# RHD2132_lvds_headstage_neuroengenharia_v.net
KiCad netlist of a schematic drawn in EAGLE
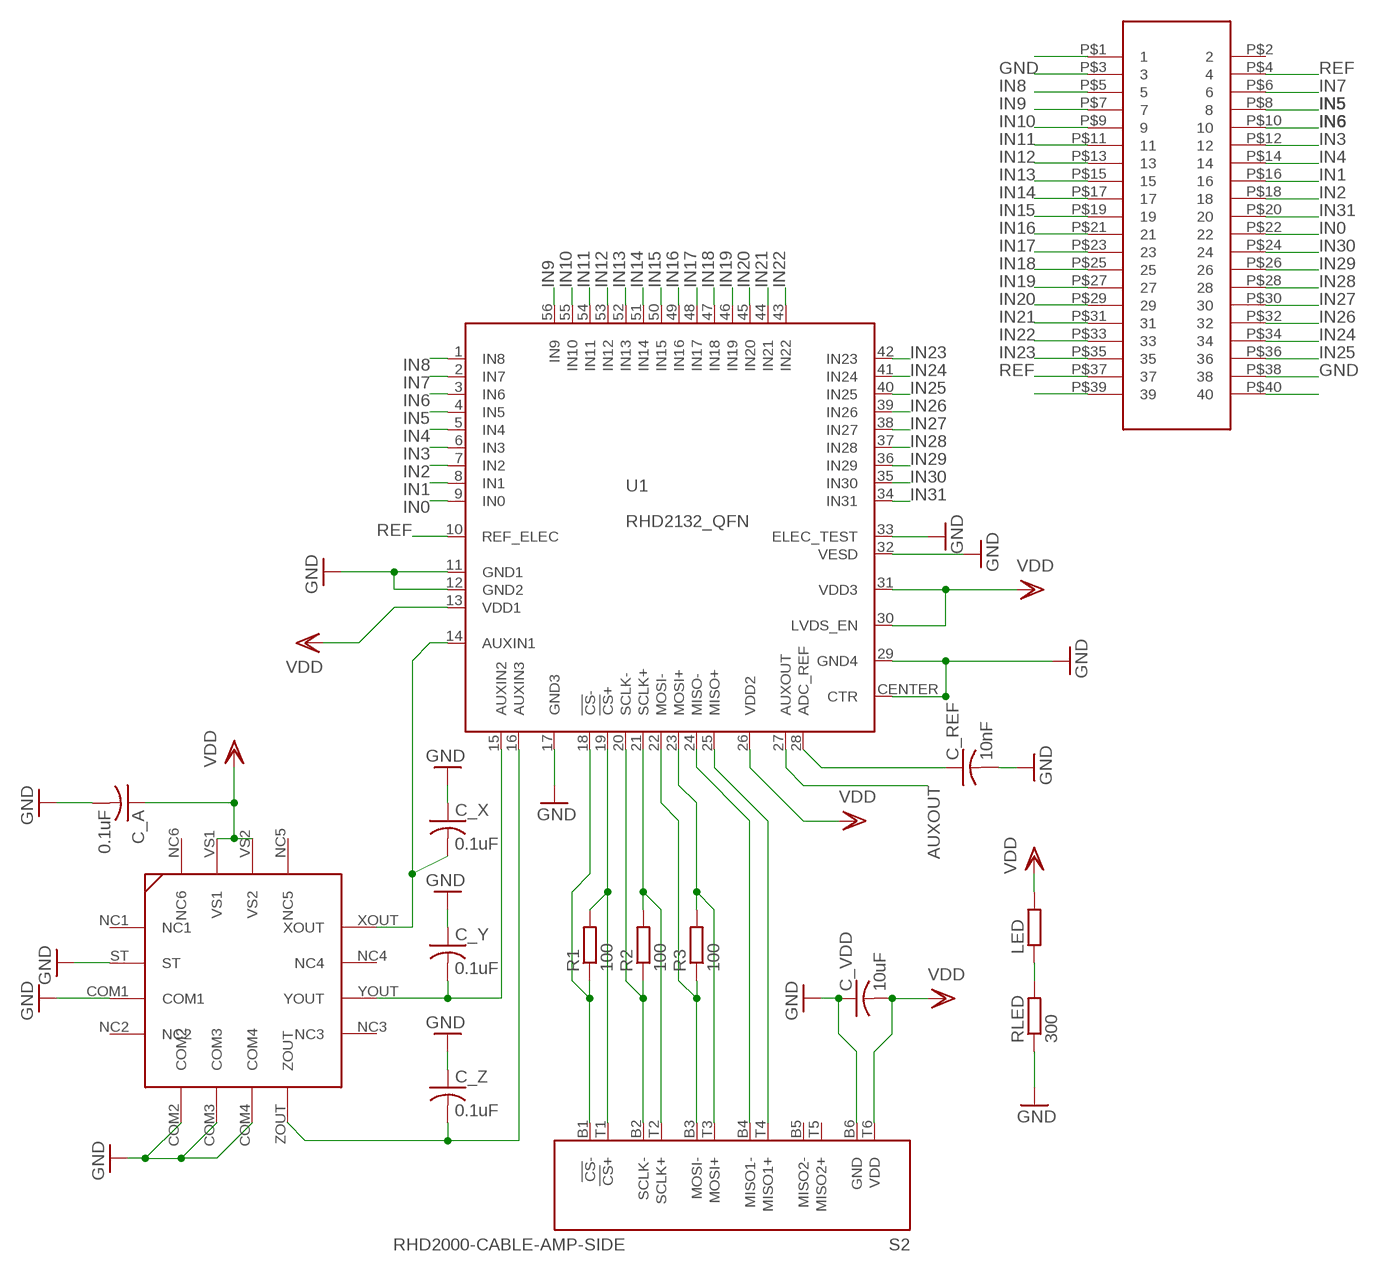
[diagram p0: schematic, sheet 1]

(export (version "E")
  (design (tool "Eeschema 10.0.6"))
  (components
    (comp (ref "C_A")
      (value "0.1uF")
      (footprint "eagle-import:C0402K")
      (libsource (lib "eagle-import") (part "C-USC0402K"))
    )
    (comp (ref "C_REF")
      (value "10nF")
      (footprint "eagle-import:C0402K")
      (libsource (lib "eagle-import") (part "C-USC0402K"))
    )
    (comp (ref "C_VDD")
      (value "10uF")
      (footprint "eagle-import:C0402K")
      (libsource (lib "eagle-import") (part "C-USC0402K"))
    )
    (comp (ref "C_X")
      (value "0.1uF")
      (footprint "eagle-import:C0402K")
      (libsource (lib "eagle-import") (part "C-USC0402K"))
    )
    (comp (ref "C_Y")
      (value "0.1uF")
      (footprint "eagle-import:C0402K")
      (libsource (lib "eagle-import") (part "C-USC0402K"))
    )
    (comp (ref "C_Z")
      (value "0.1uF")
      (footprint "eagle-import:C0402K")
      (libsource (lib "eagle-import") (part "C-USC0402K"))
    )
    (comp (ref "LED")
      (value "R-EU_R0402")
      (footprint "eagle-import:R0402")
      (libsource (lib "eagle-import") (part "R-EU_R0402"))
    )
    (comp (ref "R1")
      (value "100")
      (footprint "eagle-import:R0402")
      (libsource (lib "eagle-import") (part "R-EU_R0402"))
    )
    (comp (ref "R2")
      (value "100")
      (footprint "eagle-import:R0402")
      (libsource (lib "eagle-import") (part "R-EU_R0402"))
    )
    (comp (ref "R3")
      (value "100")
      (footprint "eagle-import:R0402")
      (libsource (lib "eagle-import") (part "R-EU_R0402"))
    )
    (comp (ref "RLED")
      (value "300")
      (footprint "eagle-import:R0402")
      (libsource (lib "eagle-import") (part "R-EU_R0402"))
    )
    (comp (ref "S2")
      (value "RHD2000-CABLE-AMP-SIDE")
      (footprint "eagle-import:OMNETICS_PZN-12-AA")
      (libsource (lib "eagle-import") (part "RHD2000-CABLE-AMP-SIDE"))
    )
    (comp (ref "U$1")
      (value "ADXL335")
      (footprint "eagle-import:ADXL335")
      (libsource (lib "eagle-import") (part "ADXL335"))
    )
    (comp (ref "U$2")
      (value "MOLEX_552010478")
      (footprint "eagle-import:MOLEX")
      (libsource (lib "eagle-import") (part "MOLEX_552010478"))
    )
    (comp (ref "U1")
      (value "RHD2132_QFN")
      (footprint "eagle-import:QFN56_8_X_8_LARGE")
      (libsource (lib "eagle-import") (part "RHD2132_QFN"))
    )
  )
  (nets
    (net (code "1") (name "/AUXOUT") (class "Default")
      (node (ref "U1") (pin "27") (pinfunction "AUXOUT_27") (pintype "tri_state"))
    )
    (net (code "2") (name "/IN0") (class "Default")
      (node (ref "U$2") (pin "P$22") (pinfunction "22_P$22") (pintype "bidirectional"))
      (node (ref "U1") (pin "9") (pinfunction "IN0_9") (pintype "input"))
    )
    (net (code "3") (name "/IN1") (class "Default")
      (node (ref "U$2") (pin "P$16") (pinfunction "16_P$16") (pintype "bidirectional"))
      (node (ref "U1") (pin "8") (pinfunction "IN1_8") (pintype "input"))
    )
    (net (code "4") (name "/IN2") (class "Default")
      (node (ref "U$2") (pin "P$18") (pinfunction "18_P$18") (pintype "bidirectional"))
      (node (ref "U1") (pin "7") (pinfunction "IN2_7") (pintype "input"))
    )
    (net (code "5") (name "/IN3") (class "Default")
      (node (ref "U$2") (pin "P$12") (pinfunction "12_P$12") (pintype "bidirectional"))
      (node (ref "U1") (pin "6") (pinfunction "IN3_6") (pintype "input"))
    )
    (net (code "6") (name "/IN4") (class "Default")
      (node (ref "U$2") (pin "P$14") (pinfunction "14_P$14") (pintype "bidirectional"))
      (node (ref "U1") (pin "5") (pinfunction "IN4_5") (pintype "input"))
    )
    (net (code "7") (name "/IN5") (class "Default")
      (node (ref "U$2") (pin "P$8") (pinfunction "8_P$8") (pintype "bidirectional"))
      (node (ref "U1") (pin "4") (pinfunction "IN5_4") (pintype "input"))
    )
    (net (code "8") (name "/IN6") (class "Default")
      (node (ref "U$2") (pin "P$10") (pinfunction "10_P$10") (pintype "bidirectional"))
      (node (ref "U1") (pin "3") (pinfunction "IN6_3") (pintype "input"))
    )
    (net (code "9") (name "/IN7") (class "Default")
      (node (ref "U$2") (pin "P$6") (pinfunction "6_P$6") (pintype "bidirectional"))
      (node (ref "U1") (pin "2") (pinfunction "IN7_2") (pintype "input"))
    )
    (net (code "10") (name "/IN8") (class "Default")
      (node (ref "U$2") (pin "P$5") (pinfunction "5_P$5") (pintype "bidirectional"))
      (node (ref "U1") (pin "1") (pinfunction "IN8_1") (pintype "input"))
    )
    (net (code "11") (name "/IN9") (class "Default")
      (node (ref "U$2") (pin "P$7") (pinfunction "7_P$7") (pintype "bidirectional"))
      (node (ref "U1") (pin "56") (pinfunction "IN9_56") (pintype "input"))
    )
    (net (code "12") (name "/IN10") (class "Default")
      (node (ref "U$2") (pin "P$9") (pinfunction "9_P$9") (pintype "bidirectional"))
      (node (ref "U1") (pin "55") (pinfunction "IN10_55") (pintype "input"))
    )
    (net (code "13") (name "/IN11") (class "Default")
      (node (ref "U$2") (pin "P$11") (pinfunction "11_P$11") (pintype "bidirectional"))
      (node (ref "U1") (pin "54") (pinfunction "IN11_54") (pintype "input"))
    )
    (net (code "14") (name "/IN12") (class "Default")
      (node (ref "U$2") (pin "P$13") (pinfunction "13_P$13") (pintype "bidirectional"))
      (node (ref "U1") (pin "53") (pinfunction "IN12_53") (pintype "input"))
    )
    (net (code "15") (name "/IN13") (class "Default")
      (node (ref "U$2") (pin "P$15") (pinfunction "15_P$15") (pintype "bidirectional"))
      (node (ref "U1") (pin "52") (pinfunction "IN13_52") (pintype "input"))
    )
    (net (code "16") (name "/IN14") (class "Default")
      (node (ref "U$2") (pin "P$17") (pinfunction "17_P$17") (pintype "bidirectional"))
      (node (ref "U1") (pin "51") (pinfunction "IN14_51") (pintype "input"))
    )
    (net (code "17") (name "/IN15") (class "Default")
      (node (ref "U$2") (pin "P$19") (pinfunction "19_P$19") (pintype "bidirectional"))
      (node (ref "U1") (pin "50") (pinfunction "IN15_50") (pintype "input"))
    )
    (net (code "18") (name "/IN16") (class "Default")
      (node (ref "U$2") (pin "P$21") (pinfunction "21_P$21") (pintype "bidirectional"))
      (node (ref "U1") (pin "49") (pinfunction "IN16_49") (pintype "input"))
    )
    (net (code "19") (name "/IN17") (class "Default")
      (node (ref "U$2") (pin "P$23") (pinfunction "23_P$23") (pintype "bidirectional"))
      (node (ref "U1") (pin "48") (pinfunction "IN17_48") (pintype "input"))
    )
    (net (code "20") (name "/IN18") (class "Default")
      (node (ref "U$2") (pin "P$25") (pinfunction "25_P$25") (pintype "bidirectional"))
      (node (ref "U1") (pin "47") (pinfunction "IN18_47") (pintype "input"))
    )
    (net (code "21") (name "/IN19") (class "Default")
      (node (ref "U$2") (pin "P$27") (pinfunction "27_P$27") (pintype "bidirectional"))
      (node (ref "U1") (pin "46") (pinfunction "IN19_46") (pintype "input"))
    )
    (net (code "22") (name "/IN20") (class "Default")
      (node (ref "U$2") (pin "P$29") (pinfunction "29_P$29") (pintype "bidirectional"))
      (node (ref "U1") (pin "45") (pinfunction "IN20_45") (pintype "input"))
    )
    (net (code "23") (name "/IN21") (class "Default")
      (node (ref "U$2") (pin "P$31") (pinfunction "31_P$31") (pintype "bidirectional"))
      (node (ref "U1") (pin "44") (pinfunction "IN21_44") (pintype "input"))
    )
    (net (code "24") (name "/IN22") (class "Default")
      (node (ref "U$2") (pin "P$33") (pinfunction "33_P$33") (pintype "bidirectional"))
      (node (ref "U1") (pin "43") (pinfunction "IN22_43") (pintype "input"))
    )
    (net (code "25") (name "/IN23") (class "Default")
      (node (ref "U$2") (pin "P$35") (pinfunction "35_P$35") (pintype "bidirectional"))
      (node (ref "U1") (pin "42") (pinfunction "IN23_42") (pintype "input"))
    )
    (net (code "26") (name "/IN24") (class "Default")
      (node (ref "U$2") (pin "P$34") (pinfunction "34_P$34") (pintype "bidirectional"))
      (node (ref "U1") (pin "41") (pinfunction "IN24_41") (pintype "input"))
    )
    (net (code "27") (name "/IN25") (class "Default")
      (node (ref "U$2") (pin "P$36") (pinfunction "36_P$36") (pintype "bidirectional"))
      (node (ref "U1") (pin "40") (pinfunction "IN25_40") (pintype "input"))
    )
    (net (code "28") (name "/IN26") (class "Default")
      (node (ref "U$2") (pin "P$32") (pinfunction "32_P$32") (pintype "bidirectional"))
      (node (ref "U1") (pin "39") (pinfunction "IN26_39") (pintype "input"))
    )
    (net (code "29") (name "/IN27") (class "Default")
      (node (ref "U$2") (pin "P$30") (pinfunction "30_P$30") (pintype "bidirectional"))
      (node (ref "U1") (pin "38") (pinfunction "IN27_38") (pintype "input"))
    )
    (net (code "30") (name "/IN28") (class "Default")
      (node (ref "U$2") (pin "P$28") (pinfunction "28_P$28") (pintype "bidirectional"))
      (node (ref "U1") (pin "37") (pinfunction "IN28_37") (pintype "input"))
    )
    (net (code "31") (name "/IN29") (class "Default")
      (node (ref "U$2") (pin "P$26") (pinfunction "26_P$26") (pintype "bidirectional"))
      (node (ref "U1") (pin "36") (pinfunction "IN29_36") (pintype "input"))
    )
    (net (code "32") (name "/IN30") (class "Default")
      (node (ref "U$2") (pin "P$24") (pinfunction "24_P$24") (pintype "bidirectional"))
      (node (ref "U1") (pin "35") (pinfunction "IN30_35") (pintype "input"))
    )
    (net (code "33") (name "/IN31") (class "Default")
      (node (ref "U$2") (pin "P$20") (pinfunction "20_P$20") (pintype "bidirectional"))
      (node (ref "U1") (pin "34") (pinfunction "IN31_34") (pintype "input"))
    )
    (net (code "34") (name "/REF") (class "Default")
      (node (ref "U$2") (pin "P$37") (pinfunction "37_P$37") (pintype "bidirectional"))
      (node (ref "U$2") (pin "P$4") (pinfunction "4_P$4") (pintype "bidirectional"))
      (node (ref "U1") (pin "10") (pinfunction "REF_ELEC_10") (pintype "input"))
    )
    (net (code "35") (name "GND") (class "Default")
      (node (ref "C_A") (pin "2") (pinfunction "2_2") (pintype "passive"))
      (node (ref "C_REF") (pin "2") (pinfunction "2_2") (pintype "passive"))
      (node (ref "C_VDD") (pin "1") (pinfunction "1_1") (pintype "passive"))
      (node (ref "C_X") (pin "1") (pinfunction "1_1") (pintype "passive"))
      (node (ref "C_Y") (pin "1") (pinfunction "1_1") (pintype "passive"))
      (node (ref "C_Z") (pin "1") (pinfunction "1_1") (pintype "passive"))
      (node (ref "RLED") (pin "1") (pinfunction "1_1") (pintype "passive"))
      (node (ref "S2") (pin "B6") (pinfunction "GND_B6") (pintype "power_in"))
      (node (ref "U$1") (pin "COM1") (pinfunction "COM1_COM1") (pintype "bidirectional"))
      (node (ref "U$1") (pin "COM2") (pinfunction "COM2_COM2") (pintype "bidirectional"))
      (node (ref "U$1") (pin "COM3") (pinfunction "COM3_COM3") (pintype "bidirectional"))
      (node (ref "U$1") (pin "COM4") (pinfunction "COM4_COM4") (pintype "bidirectional"))
      (node (ref "U$1") (pin "ST") (pinfunction "ST_ST") (pintype "bidirectional"))
      (node (ref "U$2") (pin "P$3") (pinfunction "3_P$3") (pintype "bidirectional"))
      (node (ref "U$2") (pin "P$38") (pinfunction "38_P$38") (pintype "bidirectional"))
      (node (ref "U1") (pin "11") (pinfunction "GND1_11") (pintype "power_in"))
      (node (ref "U1") (pin "12") (pinfunction "GND2_12") (pintype "power_in"))
      (node (ref "U1") (pin "17") (pinfunction "GND3_17") (pintype "power_in"))
      (node (ref "U1") (pin "29") (pinfunction "GND4_29") (pintype "power_in"))
      (node (ref "U1") (pin "32") (pinfunction "VESD_32") (pintype "power_in"))
      (node (ref "U1") (pin "33") (pinfunction "ELEC_TEST_33") (pintype "input"))
      (node (ref "U1") (pin "CENTER") (pinfunction "CTR_CENTER") (pintype "power_in"))
    )
    (net (code "36") (name "Net-(LED-Pad1)") (class "Default")
      (node (ref "LED") (pin "1") (pinfunction "1_1") (pintype "passive"))
      (node (ref "RLED") (pin "2") (pinfunction "2_2") (pintype "passive"))
    )
    (net (code "37") (name "Net-(S2-MISO1+)") (class "Default")
      (node (ref "S2") (pin "T4") (pinfunction "MISO1+_T4") (pintype "bidirectional"))
      (node (ref "U1") (pin "25") (pinfunction "MISO+_25") (pintype "output"))
    )
    (net (code "38") (name "Net-(S2-MISO1-)") (class "Default")
      (node (ref "S2") (pin "B4") (pinfunction "MISO1-_B4") (pintype "bidirectional"))
      (node (ref "U1") (pin "24") (pinfunction "MISO-_24") (pintype "output"))
    )
    (net (code "39") (name "Net-(S2-MOSI+)") (class "Default")
      (node (ref "R3") (pin "2") (pinfunction "2_2") (pintype "passive"))
      (node (ref "S2") (pin "T3") (pinfunction "MOSI+_T3") (pintype "bidirectional"))
      (node (ref "U1") (pin "23") (pinfunction "MOSI+_23") (pintype "input"))
    )
    (net (code "40") (name "Net-(S2-MOSI-)") (class "Default")
      (node (ref "R3") (pin "1") (pinfunction "1_1") (pintype "passive"))
      (node (ref "S2") (pin "B3") (pinfunction "MOSI-_B3") (pintype "bidirectional"))
      (node (ref "U1") (pin "22") (pinfunction "MOSI-_22") (pintype "input"))
    )
    (net (code "41") (name "Net-(S2-SCLK+)") (class "Default")
      (node (ref "R2") (pin "2") (pinfunction "2_2") (pintype "passive"))
      (node (ref "S2") (pin "T2") (pinfunction "SCLK+_T2") (pintype "bidirectional"))
      (node (ref "U1") (pin "21") (pinfunction "SCLK+_21") (pintype "input"))
    )
    (net (code "42") (name "Net-(S2-SCLK-)") (class "Default")
      (node (ref "R2") (pin "1") (pinfunction "1_1") (pintype "passive"))
      (node (ref "S2") (pin "B2") (pinfunction "SCLK-_B2") (pintype "bidirectional"))
      (node (ref "U1") (pin "20") (pinfunction "SCLK-_20") (pintype "input"))
    )
    (net (code "43") (name "Net-(S2-~{CS}+)") (class "Default")
      (node (ref "R1") (pin "2") (pinfunction "2_2") (pintype "passive"))
      (node (ref "S2") (pin "T1") (pinfunction "~{CS}+_T1") (pintype "bidirectional"))
      (node (ref "U1") (pin "19") (pinfunction "~{CS}+_19") (pintype "input"))
    )
    (net (code "44") (name "Net-(S2-~{CS}-)") (class "Default")
      (node (ref "R1") (pin "1") (pinfunction "1_1") (pintype "passive"))
      (node (ref "S2") (pin "B1") (pinfunction "~{CS}-_B1") (pintype "bidirectional"))
      (node (ref "U1") (pin "18") (pinfunction "~{CS}-_18") (pintype "input"))
    )
    (net (code "45") (name "Net-(U1-ADC_REF)") (class "Default")
      (node (ref "C_REF") (pin "1") (pinfunction "1_1") (pintype "passive"))
      (node (ref "U1") (pin "28") (pinfunction "ADC_REF_28") (pintype "passive"))
    )
    (net (code "46") (name "Net-(U1-AUXIN1)") (class "Default")
      (node (ref "C_X") (pin "2") (pinfunction "2_2") (pintype "passive"))
      (node (ref "U$1") (pin "XOUT") (pinfunction "XOUT_XOUT") (pintype "bidirectional"))
      (node (ref "U1") (pin "14") (pinfunction "AUXIN1_14") (pintype "input"))
    )
    (net (code "47") (name "Net-(U1-AUXIN2)") (class "Default")
      (node (ref "C_Y") (pin "2") (pinfunction "2_2") (pintype "passive"))
      (node (ref "U$1") (pin "YOUT") (pinfunction "YOUT_YOUT") (pintype "bidirectional"))
      (node (ref "U1") (pin "15") (pinfunction "AUXIN2_15") (pintype "input"))
    )
    (net (code "48") (name "Net-(U1-AUXIN3)") (class "Default")
      (node (ref "C_Z") (pin "2") (pinfunction "2_2") (pintype "passive"))
      (node (ref "U$1") (pin "ZOUT") (pinfunction "ZOUT_ZOUT") (pintype "bidirectional"))
      (node (ref "U1") (pin "16") (pinfunction "AUXIN3_16") (pintype "input"))
    )
    (net (code "49") (name "VDD") (class "Default")
      (node (ref "C_A") (pin "1") (pinfunction "1_1") (pintype "passive"))
      (node (ref "C_VDD") (pin "2") (pinfunction "2_2") (pintype "passive"))
      (node (ref "LED") (pin "2") (pinfunction "2_2") (pintype "passive"))
      (node (ref "S2") (pin "T6") (pinfunction "VDD_T6") (pintype "bidirectional"))
      (node (ref "U$1") (pin "VS1") (pinfunction "VS1_VS1") (pintype "bidirectional"))
      (node (ref "U$1") (pin "VS2") (pinfunction "VS2_VS2") (pintype "bidirectional"))
      (node (ref "U1") (pin "13") (pinfunction "VDD1_13") (pintype "power_in"))
      (node (ref "U1") (pin "26") (pinfunction "VDD2_26") (pintype "power_in"))
      (node (ref "U1") (pin "30") (pinfunction "LVDS_EN_30") (pintype "input"))
      (node (ref "U1") (pin "31") (pinfunction "VDD3_31") (pintype "power_in"))
    )
    (net (code "50") (name "unconnected-(S2-MISO2+-PadT5)") (class "Default")
      (node (ref "S2") (pin "T5") (pinfunction "MISO2+_T5") (pintype "bidirectional"))
    )
    (net (code "51") (name "unconnected-(S2-MISO2--PadB5)") (class "Default")
      (node (ref "S2") (pin "B5") (pinfunction "MISO2-_B5") (pintype "bidirectional"))
    )
    (net (code "52") (name "unconnected-(U$1-PadNC1)") (class "Default")
      (node (ref "U$1") (pin "NC1") (pinfunction "NC1_NC1") (pintype "bidirectional"))
    )
    (net (code "53") (name "unconnected-(U$1-PadNC2)") (class "Default")
      (node (ref "U$1") (pin "NC2") (pinfunction "NC2_NC2") (pintype "bidirectional"))
    )
    (net (code "54") (name "unconnected-(U$1-PadNC3)") (class "Default")
      (node (ref "U$1") (pin "NC3") (pinfunction "NC3_NC3") (pintype "bidirectional"))
    )
    (net (code "55") (name "unconnected-(U$1-PadNC4)") (class "Default")
      (node (ref "U$1") (pin "NC4") (pinfunction "NC4_NC4") (pintype "bidirectional"))
    )
    (net (code "56") (name "unconnected-(U$1-PadNC5)") (class "Default")
      (node (ref "U$1") (pin "NC5") (pinfunction "NC5_NC5") (pintype "bidirectional"))
    )
    (net (code "57") (name "unconnected-(U$1-PadNC6)") (class "Default")
      (node (ref "U$1") (pin "NC6") (pinfunction "NC6_NC6") (pintype "bidirectional"))
    )
    (net (code "58") (name "unconnected-(U$2-1-PadP$1)") (class "Default")
      (node (ref "U$2") (pin "P$1") (pinfunction "1_P$1") (pintype "bidirectional"))
    )
    (net (code "59") (name "unconnected-(U$2-2-PadP$2)") (class "Default")
      (node (ref "U$2") (pin "P$2") (pinfunction "2_P$2") (pintype "bidirectional"))
    )
    (net (code "60") (name "unconnected-(U$2-39-PadP$39)") (class "Default")
      (node (ref "U$2") (pin "P$39") (pinfunction "39_P$39") (pintype "bidirectional"))
    )
    (net (code "61") (name "unconnected-(U$2-40-PadP$40)") (class "Default")
      (node (ref "U$2") (pin "P$40") (pinfunction "40_P$40") (pintype "bidirectional"))
    )
  )
)
